# multishield.net
KiCad netlist of a schematic drawn in EAGLE
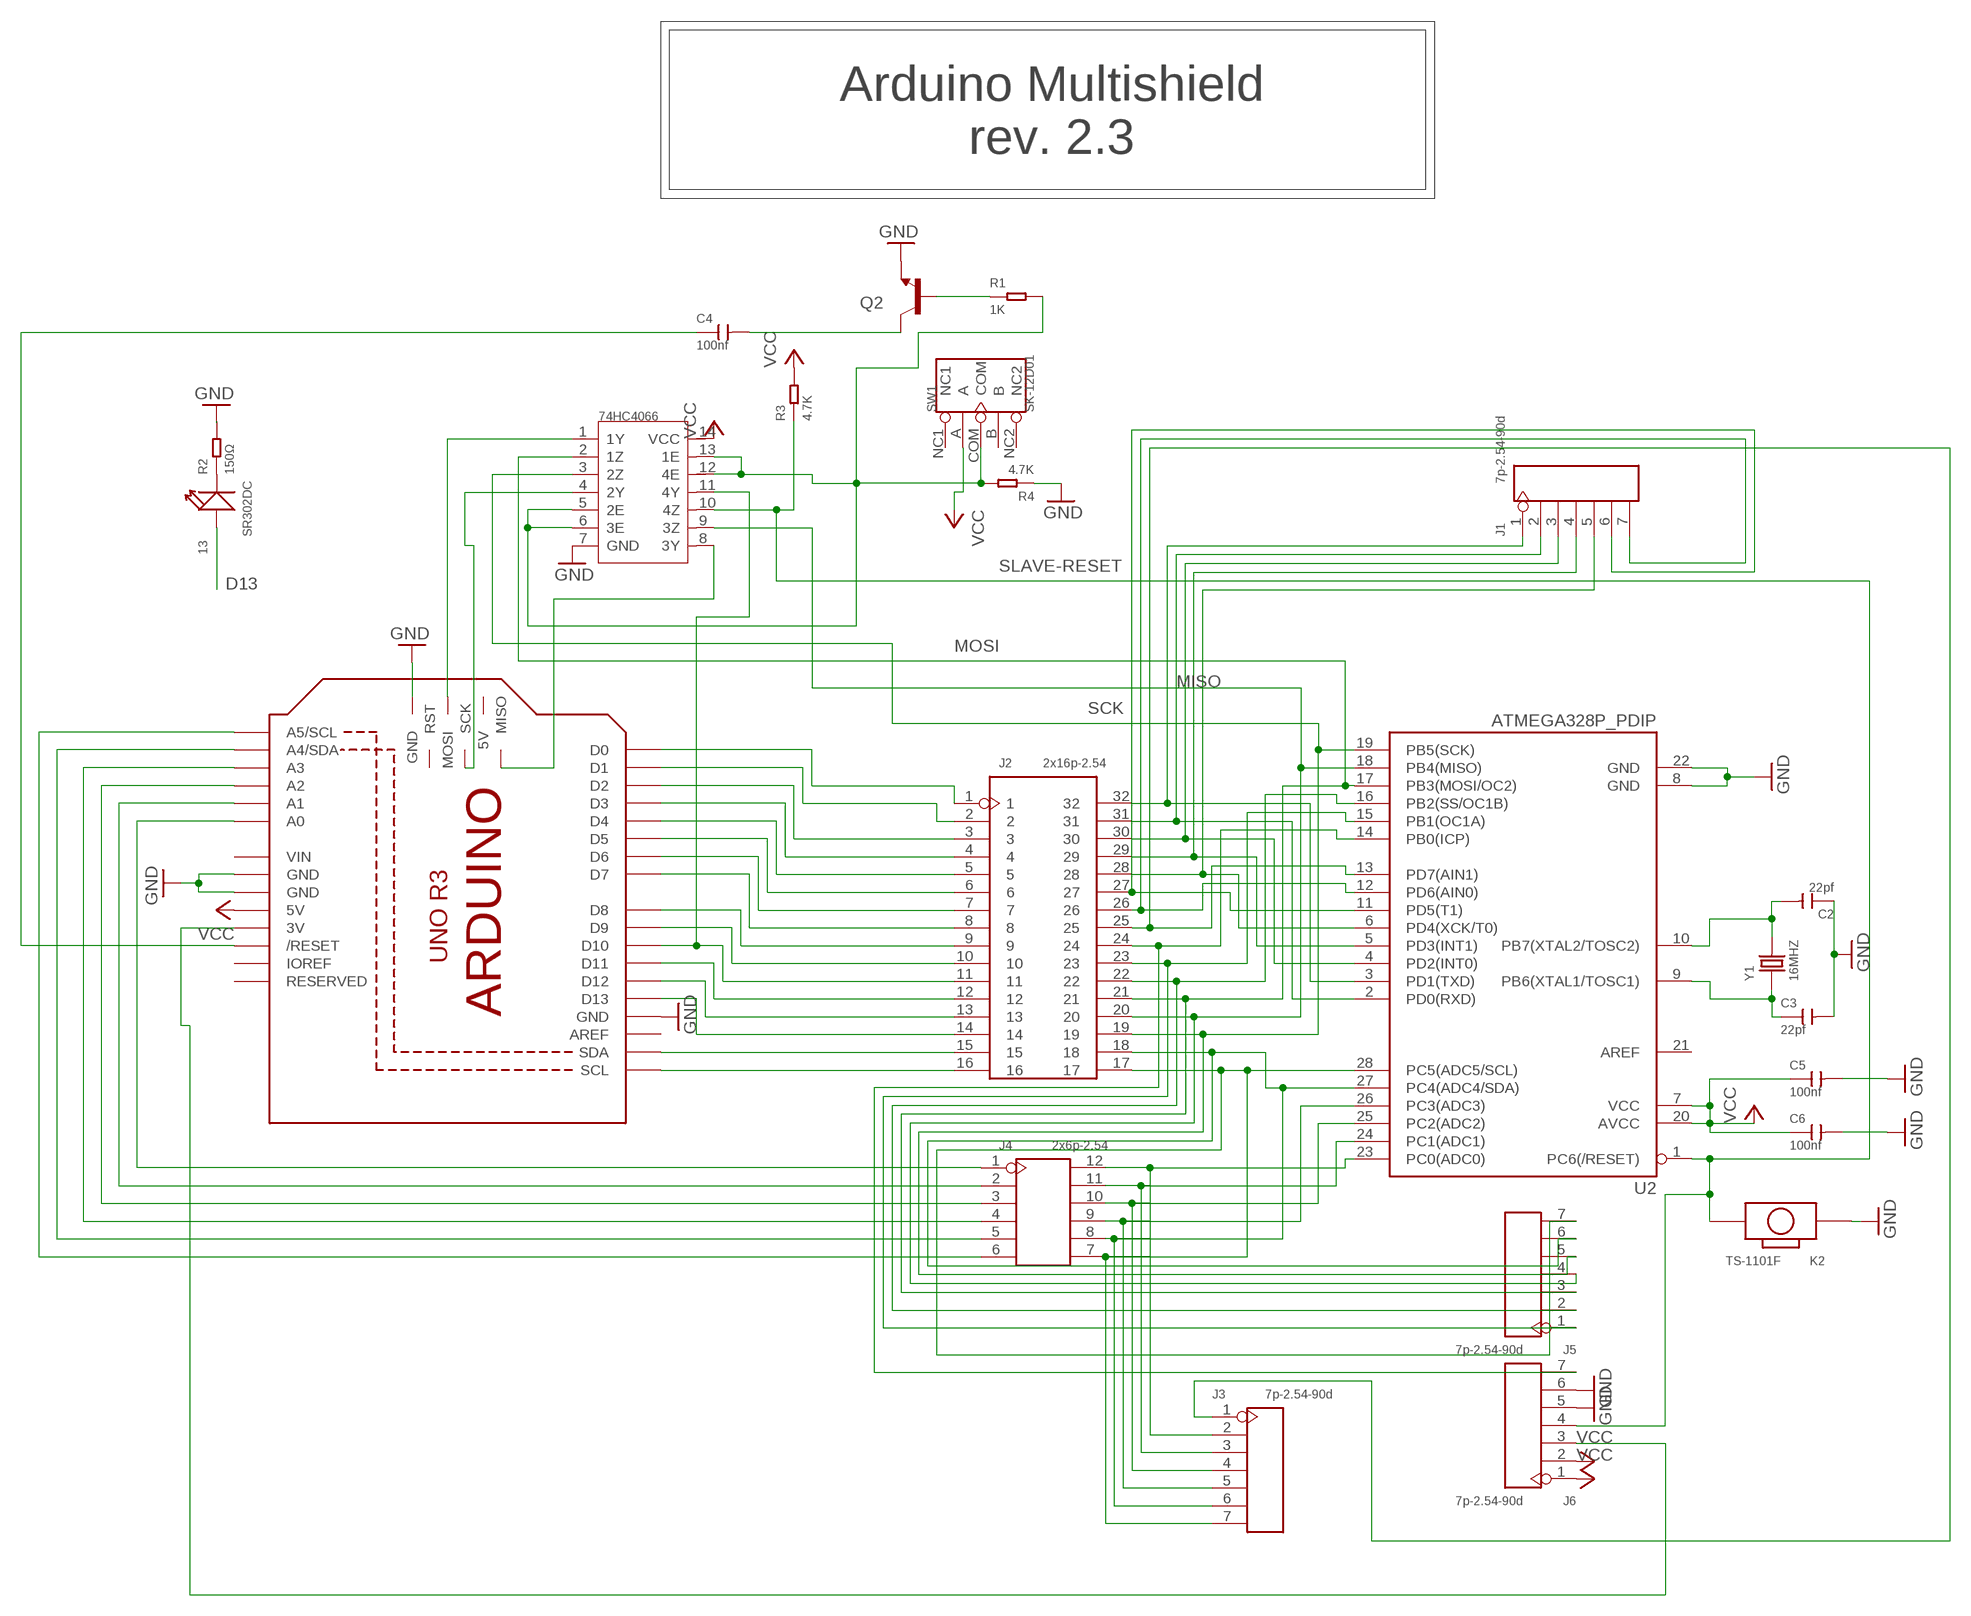
[diagram p0: schematic, sheet 1]

(export (version "E")
  (design (tool "Eeschema 10.0.6"))
  (components
    (comp (ref "13")
      (value "SR302DC")
      (footprint "eagle-import:LED2-2.54-D3.0MM")
      (libsource (lib "eagle-import") (part "DIP-LED-RED-RED(2P-D3MM)"))
    )
    (comp (ref "C2")
      (value "22pf")
      (footprint "eagle-import:CERAMIC-2.54")
      (fields (field (name "MPN") "CS1-D5Y5V2A104ZSP"))
      (libsource (lib "eagle-import") (part "DIP-CERAMIC-DISC-22PF-50V-10%-NPO(D4.0MM)"))
    )
    (comp (ref "C3")
      (value "22pf")
      (footprint "eagle-import:CERAMIC-2.54")
      (fields (field (name "MPN") "CS1-D5Y5V2A104ZSP"))
      (libsource (lib "eagle-import") (part "DIP-CERAMIC-DISC-22PF-50V-10%-NPO(D4.0MM)"))
    )
    (comp (ref "C4")
      (value "100nf")
      (footprint "eagle-import:CERAMIC-2.54")
      (fields (field (name "MPN") "CC1-F5SL2A101KSPW"))
      (libsource (lib "eagle-import") (part "DIP-CERAMIC-DISC-100NF-50V-Y5V(D5.0MM)"))
    )
    (comp (ref "C5")
      (value "100nf")
      (footprint "eagle-import:CERAMIC-2.54")
      (fields (field (name "MPN") "CC1-F5SL2A101KSPW"))
      (libsource (lib "eagle-import") (part "DIP-CERAMIC-DISC-100NF-50V-Y5V(D5.0MM)"))
    )
    (comp (ref "C6")
      (value "100nf")
      (footprint "eagle-import:CERAMIC-2.54")
      (fields (field (name "MPN") "CC1-F5SL2A101KSPW"))
      (libsource (lib "eagle-import") (part "DIP-CERAMIC-DISC-100NF-50V-Y5V(D5.0MM)"))
    )
    (comp (ref "J1")
      (value "7p-2.54-90d")
      (footprint "eagle-import:H7-2.54-90D-MALE")
      (fields (field (name "MPN") "P125-1107A0BR138A1"))
      (libsource (lib "eagle-import") (part "DIP-BLACK-MALE-HEADER(7P-2.54-90D)"))
    )
    (comp (ref "J2")
      (value "2x16p-2.54")
      (footprint "eagle-import:H2X16-2.54")
      (fields (field (name "MPN") "P125-1232A0AS116A1"))
      (libsource (lib "eagle-import") (part "DIP-BLACK-MALE-HEADER-VERT(2X16P-2.54)"))
    )
    (comp (ref "J3")
      (value "7p-2.54-90d")
      (footprint "eagle-import:H7-2.54-90D-MALE")
      (fields (field (name "MPN") "P125-1107A0BR138A1"))
      (libsource (lib "eagle-import") (part "DIP-BLACK-MALE-HEADER(7P-2.54-90D)"))
    )
    (comp (ref "J4")
      (value "2x6p-2.54")
      (footprint "eagle-import:H2X6-2.54")
      (fields (field (name "MPN") "P125-1212A0AS116A1"))
      (libsource (lib "eagle-import") (part "DIP-BLACK-MALE-HEADER(2X6P-2.54)"))
    )
    (comp (ref "J5")
      (value "7p-2.54-90d")
      (footprint "eagle-import:H7-2.54-90D-MALE")
      (fields (field (name "MPN") "P125-1107A0BR138A1"))
      (libsource (lib "eagle-import") (part "DIP-BLACK-MALE-HEADER(7P-2.54-90D)"))
    )
    (comp (ref "J6")
      (value "7p-2.54-90d")
      (footprint "eagle-import:H7-2.54-90D-MALE")
      (fields (field (name "MPN") "P125-1107A0BR138A1"))
      (libsource (lib "eagle-import") (part "DIP-BLACK-MALE-HEADER(7P-2.54-90D)"))
    )
    (comp (ref "K2")
      (value "TS-1101F")
      (footprint "eagle-import:SW2-3.4X6.0X3.55MM-90D")
      (libsource (lib "eagle-import") (part "DIP-BUTTON-FRONT-WHITE(2P-3.4X6MM)"))
    )
    (comp (ref "M1")
      (value "ARDUINO_R3_ICSP")
      (footprint "eagle-import:ARDUINOR3_ICSP")
      (libsource (lib "eagle-import") (part "ARDUINO_R3_ICSP"))
    )
    (comp (ref "Q2")
      (value "TRANSISTOR_NPNBC547")
      (footprint "eagle-import:TO-92-AMMO")
      (libsource (lib "eagle-import") (part "TRANSISTOR_NPNBC547"))
    )
    (comp (ref "R1")
      (value "1K")
      (footprint "eagle-import:PR-D2.3XL6.5MM")
      (fields (field (name "MPN") "FHCFR-1/4W-102J"))
      (libsource (lib "eagle-import") (part "DIP-RES-1K-5%-1/4W(PR-D2.3XL6.5MM)"))
    )
    (comp (ref "R2")
      (value "150Ω")
      (footprint "eagle-import:PR-D2.3XL6.5MM")
      (fields (field (name "MPN") "FHCFR-1/4W-102J"))
      (libsource (lib "eagle-import") (part "DIP-RES-1K-5%-1/4W(PR-D2.3XL6.5MM)"))
    )
    (comp (ref "R3")
      (value "4.7K")
      (footprint "eagle-import:PR-D2.3XL6.5MM")
      (fields (field (name "MPN") "FHCFR-1/4W-472J"))
      (libsource (lib "eagle-import") (part "DIP-RES-4.7K-5%-1/4W(PR-D2.3XL6.5MM)"))
    )
    (comp (ref "R4")
      (value "4.7K")
      (footprint "eagle-import:PR-D2.3XL6.5MM")
      (fields (field (name "MPN") "FHCFR-1/4W-472J"))
      (libsource (lib "eagle-import") (part "DIP-RES-4.7K-5%-1/4W(PR-D2.3XL6.5MM)"))
    )
    (comp (ref "SW1")
      (value "SK-12D01")
      (footprint "eagle-import:SW5-2.0-8.8X4.4X4.7MM-90D")
      (libsource (lib "eagle-import") (part "DIP-TOGGLE-SWITCH-ON-ON(3+2P-8.8X4.6MM)"))
    )
    (comp (ref "U1")
      (value "AD595AQ-DIP14")
      (footprint "eagle-import:DIP14-2.54-17.24X6.35MM")
      (fields (field (name "MPN") "AD595AQ"))
      (libsource (lib "eagle-import") (part "74HC4066(DIP14)"))
    )
    (comp (ref "U2")
      (value "ATMEGA328P_PDIP")
      (footprint "eagle-import:DIL28-3")
      (libsource (lib "eagle-import") (part "ATMEGA328P_PDIP"))
    )
    (comp (ref "Y1")
      (value "16MHZ")
      (footprint "eagle-import:HC49US")
      (fields (field (name "MPN") "49S/18PF"))
      (libsource (lib "eagle-import") (part "DIP-CRYSTAL-16MHZ-18PF-30PPM-50R(HC49US)"))
    )
  )
  (nets
    (net (code "1") (name "/MISO") (class "Default")
      (node (ref "J2") (pin "20") (pinfunction "20_20") (pintype "bidirectional"))
      (node (ref "J5") (pin "4") (pinfunction "4_4") (pintype "bidirectional"))
      (node (ref "U1") (pin "9") (pinfunction "3Z_9") (pintype "bidirectional"))
      (node (ref "U2") (pin "18") (pinfunction "PB4(MISO)_18") (pintype "bidirectional"))
    )
    (net (code "2") (name "/MOSI") (class "Default")
      (node (ref "J2") (pin "21") (pinfunction "21_21") (pintype "bidirectional"))
      (node (ref "J5") (pin "3") (pinfunction "3_3") (pintype "bidirectional"))
      (node (ref "U1") (pin "2") (pinfunction "1Z_2") (pintype "bidirectional"))
      (node (ref "U2") (pin "17") (pinfunction "PB3(MOSI/OC2)_17") (pintype "bidirectional"))
    )
    (net (code "3") (name "/SCK") (class "Default")
      (node (ref "13") (pin "A") (pinfunction "+_A") (pintype "passive"))
      (node (ref "J2") (pin "19") (pinfunction "19_19") (pintype "bidirectional"))
      (node (ref "J5") (pin "5") (pinfunction "5_5") (pintype "bidirectional"))
      (node (ref "U1") (pin "3") (pinfunction "2Z_3") (pintype "bidirectional"))
      (node (ref "U2") (pin "19") (pinfunction "PB5(SCK)_19") (pintype "bidirectional"))
    )
    (net (code "4") (name "/SLAVE-RESET") (class "Default")
      (node (ref "J6") (pin "4") (pinfunction "4_4") (pintype "bidirectional"))
      (node (ref "K2") (pin "P$2") (pinfunction "2_P$2") (pintype "bidirectional"))
      (node (ref "R3") (pin "1") (pinfunction "1_1") (pintype "passive"))
      (node (ref "U1") (pin "10") (pinfunction "4Z_10") (pintype "bidirectional"))
      (node (ref "U2") (pin "1") (pinfunction "PC6(/RESET)_1") (pintype "bidirectional"))
    )
    (net (code "5") (name "/VIN") (class "Default")
      (node (ref "M1") (pin "VIN") (pinfunction "VIN_VIN") (pintype "power_in"))
    )
    (net (code "6") (name "GND") (class "Default")
      (node (ref "C2") (pin "1") (pinfunction "1_1") (pintype "passive"))
      (node (ref "C3") (pin "2") (pinfunction "2_2") (pintype "passive"))
      (node (ref "C5") (pin "2") (pinfunction "2_2") (pintype "passive"))
      (node (ref "C6") (pin "2") (pinfunction "2_2") (pintype "passive"))
      (node (ref "J6") (pin "5") (pinfunction "5_5") (pintype "bidirectional"))
      (node (ref "J6") (pin "6") (pinfunction "6_6") (pintype "bidirectional"))
      (node (ref "K2") (pin "P$1") (pinfunction "1_P$1") (pintype "bidirectional"))
      (node (ref "M1") (pin "GND") (pinfunction "GND_GND") (pintype "power_in"))
      (node (ref "M1") (pin "GND@1") (pinfunction "GND_GND@1") (pintype "power_in"))
      (node (ref "M1") (pin "GND@2") (pinfunction "GND_GND@2") (pintype "passive"))
      (node (ref "M1") (pin "GND@3") (pinfunction "GND_GND@3") (pintype "power_in"))
      (node (ref "Q2") (pin "3") (pinfunction "E_3") (pintype "passive"))
      (node (ref "R2") (pin "2") (pinfunction "2_2") (pintype "passive"))
      (node (ref "R4") (pin "1") (pinfunction "1_1") (pintype "passive"))
      (node (ref "U1") (pin "7") (pinfunction "GND_7") (pintype "bidirectional"))
      (node (ref "U2") (pin "22") (pinfunction "GND_22") (pintype "bidirectional"))
      (node (ref "U2") (pin "8") (pinfunction "GND_8") (pintype "bidirectional"))
    )
    (net (code "7") (name "Net-(13--)") (class "Default")
      (node (ref "13") (pin "K") (pinfunction "-_K") (pintype "passive"))
      (node (ref "R2") (pin "1") (pinfunction "1_1") (pintype "passive"))
    )
    (net (code "8") (name "Net-(J2-Pad1)") (class "Default")
      (node (ref "J2") (pin "1") (pinfunction "1_1") (pintype "bidirectional"))
      (node (ref "M1") (pin "D0") (pinfunction "D0_D0") (pintype "bidirectional"))
    )
    (net (code "9") (name "Net-(J2-Pad2)") (class "Default")
      (node (ref "J2") (pin "2") (pinfunction "2_2") (pintype "bidirectional"))
      (node (ref "M1") (pin "D1") (pinfunction "D1_D1") (pintype "bidirectional"))
    )
    (net (code "10") (name "Net-(J2-Pad3)") (class "Default")
      (node (ref "J2") (pin "3") (pinfunction "3_3") (pintype "bidirectional"))
      (node (ref "M1") (pin "D2") (pinfunction "D2_D2") (pintype "bidirectional"))
    )
    (net (code "11") (name "Net-(J2-Pad4)") (class "Default")
      (node (ref "J2") (pin "4") (pinfunction "4_4") (pintype "bidirectional"))
      (node (ref "M1") (pin "D3") (pinfunction "D3_D3") (pintype "bidirectional"))
    )
    (net (code "12") (name "Net-(J2-Pad5)") (class "Default")
      (node (ref "J2") (pin "5") (pinfunction "5_5") (pintype "bidirectional"))
      (node (ref "M1") (pin "D4") (pinfunction "D4_D4") (pintype "bidirectional"))
    )
    (net (code "13") (name "Net-(J2-Pad6)") (class "Default")
      (node (ref "J2") (pin "6") (pinfunction "6_6") (pintype "bidirectional"))
      (node (ref "M1") (pin "D5") (pinfunction "D5_D5") (pintype "bidirectional"))
    )
    (net (code "14") (name "Net-(J2-Pad7)") (class "Default")
      (node (ref "J2") (pin "7") (pinfunction "7_7") (pintype "bidirectional"))
      (node (ref "M1") (pin "D6") (pinfunction "D6_D6") (pintype "bidirectional"))
    )
    (net (code "15") (name "Net-(J2-Pad8)") (class "Default")
      (node (ref "J2") (pin "8") (pinfunction "8_8") (pintype "bidirectional"))
      (node (ref "M1") (pin "D7") (pinfunction "D7_D7") (pintype "bidirectional"))
    )
    (net (code "16") (name "Net-(J2-Pad9)") (class "Default")
      (node (ref "J2") (pin "9") (pinfunction "9_9") (pintype "bidirectional"))
      (node (ref "M1") (pin "D8") (pinfunction "D8_D8") (pintype "bidirectional"))
    )
    (net (code "17") (name "Net-(J2-Pad10)") (class "Default")
      (node (ref "J2") (pin "10") (pinfunction "10_10") (pintype "bidirectional"))
      (node (ref "M1") (pin "D9") (pinfunction "D9_D9") (pintype "bidirectional"))
    )
    (net (code "18") (name "Net-(J2-Pad12)") (class "Default")
      (node (ref "J2") (pin "12") (pinfunction "12_12") (pintype "bidirectional"))
      (node (ref "M1") (pin "D11") (pinfunction "D11_D11") (pintype "bidirectional"))
    )
    (net (code "19") (name "Net-(J2-Pad13)") (class "Default")
      (node (ref "J2") (pin "13") (pinfunction "13_13") (pintype "bidirectional"))
      (node (ref "M1") (pin "D12") (pinfunction "D12_D12") (pintype "bidirectional"))
    )
    (net (code "20") (name "Net-(J2-Pad14)") (class "Default")
      (node (ref "J2") (pin "14") (pinfunction "14_14") (pintype "bidirectional"))
      (node (ref "M1") (pin "D13") (pinfunction "D13_D13") (pintype "bidirectional"))
    )
    (net (code "21") (name "Net-(J2-Pad15)") (class "Default")
      (node (ref "J2") (pin "15") (pinfunction "15_15") (pintype "bidirectional"))
      (node (ref "M1") (pin "SDA") (pinfunction "SDA_SDA") (pintype "bidirectional"))
    )
    (net (code "22") (name "Net-(J2-Pad16)") (class "Default")
      (node (ref "J2") (pin "16") (pinfunction "16_16") (pintype "bidirectional"))
      (node (ref "M1") (pin "SCL") (pinfunction "SCL_SCL") (pintype "bidirectional"))
    )
    (net (code "23") (name "Net-(J4-Pad1)") (class "Default")
      (node (ref "J4") (pin "1") (pinfunction "1_1") (pintype "bidirectional"))
      (node (ref "M1") (pin "A0") (pinfunction "A0_A0") (pintype "bidirectional"))
    )
    (net (code "24") (name "Net-(J4-Pad2)") (class "Default")
      (node (ref "J4") (pin "2") (pinfunction "2_2") (pintype "bidirectional"))
      (node (ref "M1") (pin "A1") (pinfunction "A1_A1") (pintype "bidirectional"))
    )
    (net (code "25") (name "Net-(J4-Pad3)") (class "Default")
      (node (ref "J4") (pin "3") (pinfunction "3_3") (pintype "bidirectional"))
      (node (ref "M1") (pin "A2") (pinfunction "A2_A2") (pintype "bidirectional"))
    )
    (net (code "26") (name "Net-(J4-Pad4)") (class "Default")
      (node (ref "J4") (pin "4") (pinfunction "4_4") (pintype "bidirectional"))
      (node (ref "M1") (pin "A3") (pinfunction "A3_A3") (pintype "bidirectional"))
    )
    (net (code "27") (name "Net-(J6-Pad3)") (class "Default")
      (node (ref "J6") (pin "3") (pinfunction "3_3") (pintype "bidirectional"))
      (node (ref "M1") (pin "3V") (pinfunction "3V_3V") (pintype "power_in"))
    )
    (net (code "28") (name "Net-(M1-A4{slash}SDA)") (class "Default")
      (node (ref "J4") (pin "5") (pinfunction "5_5") (pintype "bidirectional"))
      (node (ref "M1") (pin "A4") (pinfunction "A4/SDA_A4") (pintype "bidirectional"))
    )
    (net (code "29") (name "Net-(M1-A5{slash}SCL)") (class "Default")
      (node (ref "J4") (pin "6") (pinfunction "6_6") (pintype "bidirectional"))
      (node (ref "M1") (pin "A5") (pinfunction "A5/SCL_A5") (pintype "bidirectional"))
    )
    (net (code "30") (name "Net-(M1-{slash}RESET)") (class "Default")
      (node (ref "C4") (pin "1") (pinfunction "1_1") (pintype "passive"))
      (node (ref "M1") (pin "RESET") (pinfunction "/RESET_RESET") (pintype "bidirectional"))
    )
    (net (code "31") (name "Net-(Q2-B)") (class "Default")
      (node (ref "Q2") (pin "2") (pinfunction "B_2") (pintype "passive"))
      (node (ref "R1") (pin "1") (pinfunction "1_1") (pintype "passive"))
    )
    (net (code "32") (name "Net-(Q2-C)") (class "Default")
      (node (ref "C4") (pin "2") (pinfunction "2_2") (pintype "passive"))
      (node (ref "Q2") (pin "1") (pinfunction "C_1") (pintype "passive"))
    )
    (net (code "33") (name "Net-(U1-1E)") (class "Default")
      (node (ref "R1") (pin "2") (pinfunction "2_2") (pintype "passive"))
      (node (ref "R4") (pin "2") (pinfunction "2_2") (pintype "passive"))
      (node (ref "SW1") (pin "COM") (pinfunction "COM_COM") (pintype "bidirectional"))
      (node (ref "U1") (pin "12") (pinfunction "4E_12") (pintype "bidirectional"))
      (node (ref "U1") (pin "13") (pinfunction "1E_13") (pintype "bidirectional"))
      (node (ref "U1") (pin "5") (pinfunction "2E_5") (pintype "bidirectional"))
      (node (ref "U1") (pin "6") (pinfunction "3E_6") (pintype "bidirectional"))
    )
    (net (code "34") (name "Net-(U1-1Y)") (class "Default")
      (node (ref "M1") (pin "MOSI") (pinfunction "MOSI_MOSI") (pintype "passive"))
      (node (ref "U1") (pin "1") (pinfunction "1Y_1") (pintype "bidirectional"))
    )
    (net (code "35") (name "Net-(U1-2Y)") (class "Default")
      (node (ref "M1") (pin "SCK") (pinfunction "SCK_SCK") (pintype "passive"))
      (node (ref "U1") (pin "4") (pinfunction "2Y_4") (pintype "bidirectional"))
    )
    (net (code "36") (name "Net-(U1-3Y)") (class "Default")
      (node (ref "M1") (pin "MISO") (pinfunction "MISO_MISO") (pintype "passive"))
      (node (ref "U1") (pin "8") (pinfunction "3Y_8") (pintype "bidirectional"))
    )
    (net (code "37") (name "Net-(U1-4Y)") (class "Default")
      (node (ref "J2") (pin "11") (pinfunction "11_11") (pintype "bidirectional"))
      (node (ref "M1") (pin "D10") (pinfunction "D10_D10") (pintype "bidirectional"))
      (node (ref "U1") (pin "11") (pinfunction "4Y_11") (pintype "bidirectional"))
    )
    (net (code "38") (name "Net-(U2-PB0(ICP))") (class "Default")
      (node (ref "J2") (pin "24") (pinfunction "24_24") (pintype "bidirectional"))
      (node (ref "J6") (pin "7") (pinfunction "7_7") (pintype "bidirectional"))
      (node (ref "U2") (pin "14") (pinfunction "PB0(ICP)_14") (pintype "bidirectional"))
    )
    (net (code "39") (name "Net-(U2-PB1(OC1A))") (class "Default")
      (node (ref "J2") (pin "23") (pinfunction "23_23") (pintype "bidirectional"))
      (node (ref "J5") (pin "1") (pinfunction "1_1") (pintype "bidirectional"))
      (node (ref "U2") (pin "15") (pinfunction "PB1(OC1A)_15") (pintype "bidirectional"))
    )
    (net (code "40") (name "Net-(U2-PB2(SS{slash}OC1B))") (class "Default")
      (node (ref "J2") (pin "22") (pinfunction "22_22") (pintype "bidirectional"))
      (node (ref "J5") (pin "2") (pinfunction "2_2") (pintype "bidirectional"))
      (node (ref "U2") (pin "16") (pinfunction "PB2(SS/OC1B)_16") (pintype "bidirectional"))
    )
    (net (code "41") (name "Net-(U2-PB6(XTAL1{slash}TOSC1))") (class "Default")
      (node (ref "C3") (pin "1") (pinfunction "1_1") (pintype "passive"))
      (node (ref "U2") (pin "9") (pinfunction "PB6(XTAL1/TOSC1)_9") (pintype "bidirectional"))
      (node (ref "Y1") (pin "1") (pinfunction "1_1") (pintype "passive"))
    )
    (net (code "42") (name "Net-(U2-PB7(XTAL2{slash}TOSC2))") (class "Default")
      (node (ref "C2") (pin "2") (pinfunction "2_2") (pintype "passive"))
      (node (ref "U2") (pin "10") (pinfunction "PB7(XTAL2/TOSC2)_10") (pintype "bidirectional"))
      (node (ref "Y1") (pin "2") (pinfunction "2_2") (pintype "passive"))
    )
    (net (code "43") (name "Net-(U2-PC0(ADC0))") (class "Default")
      (node (ref "J3") (pin "2") (pinfunction "2_2") (pintype "bidirectional"))
      (node (ref "J4") (pin "12") (pinfunction "12_12") (pintype "bidirectional"))
      (node (ref "U2") (pin "23") (pinfunction "PC0(ADC0)_23") (pintype "bidirectional"))
    )
    (net (code "44") (name "Net-(U2-PC1(ADC1))") (class "Default")
      (node (ref "J3") (pin "3") (pinfunction "3_3") (pintype "bidirectional"))
      (node (ref "J4") (pin "11") (pinfunction "11_11") (pintype "bidirectional"))
      (node (ref "U2") (pin "24") (pinfunction "PC1(ADC1)_24") (pintype "bidirectional"))
    )
    (net (code "45") (name "Net-(U2-PC2(ADC2))") (class "Default")
      (node (ref "J3") (pin "4") (pinfunction "4_4") (pintype "bidirectional"))
      (node (ref "J4") (pin "10") (pinfunction "10_10") (pintype "bidirectional"))
      (node (ref "U2") (pin "25") (pinfunction "PC2(ADC2)_25") (pintype "bidirectional"))
    )
    (net (code "46") (name "Net-(U2-PC3(ADC3))") (class "Default")
      (node (ref "J3") (pin "5") (pinfunction "5_5") (pintype "bidirectional"))
      (node (ref "J4") (pin "9") (pinfunction "9_9") (pintype "bidirectional"))
      (node (ref "U2") (pin "26") (pinfunction "PC3(ADC3)_26") (pintype "bidirectional"))
    )
    (net (code "47") (name "Net-(U2-PC4(ADC4{slash}SDA))") (class "Default")
      (node (ref "J2") (pin "18") (pinfunction "18_18") (pintype "bidirectional"))
      (node (ref "J3") (pin "6") (pinfunction "6_6") (pintype "bidirectional"))
      (node (ref "J4") (pin "8") (pinfunction "8_8") (pintype "bidirectional"))
      (node (ref "J5") (pin "6") (pinfunction "6_6") (pintype "bidirectional"))
      (node (ref "U2") (pin "27") (pinfunction "PC4(ADC4/SDA)_27") (pintype "bidirectional"))
    )
    (net (code "48") (name "Net-(U2-PC5(ADC5{slash}SCL))") (class "Default")
      (node (ref "J2") (pin "17") (pinfunction "17_17") (pintype "bidirectional"))
      (node (ref "J3") (pin "7") (pinfunction "7_7") (pintype "bidirectional"))
      (node (ref "J4") (pin "7") (pinfunction "7_7") (pintype "bidirectional"))
      (node (ref "J5") (pin "7") (pinfunction "7_7") (pintype "bidirectional"))
      (node (ref "U2") (pin "28") (pinfunction "PC5(ADC5/SCL)_28") (pintype "bidirectional"))
    )
    (net (code "49") (name "Net-(U2-PD0(RXD))") (class "Default")
      (node (ref "J1") (pin "2") (pinfunction "2_2") (pintype "bidirectional"))
      (node (ref "J2") (pin "31") (pinfunction "31_31") (pintype "bidirectional"))
      (node (ref "U2") (pin "2") (pinfunction "PD0(RXD)_2") (pintype "bidirectional"))
    )
    (net (code "50") (name "Net-(U2-PD1(TXD))") (class "Default")
      (node (ref "J1") (pin "1") (pinfunction "1_1") (pintype "bidirectional"))
      (node (ref "J2") (pin "32") (pinfunction "32_32") (pintype "bidirectional"))
      (node (ref "U2") (pin "3") (pinfunction "PD1(TXD)_3") (pintype "bidirectional"))
    )
    (net (code "51") (name "Net-(U2-PD2(INT0))") (class "Default")
      (node (ref "J1") (pin "3") (pinfunction "3_3") (pintype "bidirectional"))
      (node (ref "J2") (pin "30") (pinfunction "30_30") (pintype "bidirectional"))
      (node (ref "U2") (pin "4") (pinfunction "PD2(INT0)_4") (pintype "bidirectional"))
    )
    (net (code "52") (name "Net-(U2-PD3(INT1))") (class "Default")
      (node (ref "J1") (pin "4") (pinfunction "4_4") (pintype "bidirectional"))
      (node (ref "J2") (pin "29") (pinfunction "29_29") (pintype "bidirectional"))
      (node (ref "U2") (pin "5") (pinfunction "PD3(INT1)_5") (pintype "bidirectional"))
    )
    (net (code "53") (name "Net-(U2-PD4(XCK{slash}T0))") (class "Default")
      (node (ref "J1") (pin "5") (pinfunction "5_5") (pintype "bidirectional"))
      (node (ref "J2") (pin "28") (pinfunction "28_28") (pintype "bidirectional"))
      (node (ref "U2") (pin "6") (pinfunction "PD4(XCK/T0)_6") (pintype "bidirectional"))
    )
    (net (code "54") (name "Net-(U2-PD5(T1))") (class "Default")
      (node (ref "J1") (pin "6") (pinfunction "6_6") (pintype "bidirectional"))
      (node (ref "J2") (pin "27") (pinfunction "27_27") (pintype "bidirectional"))
      (node (ref "U2") (pin "11") (pinfunction "PD5(T1)_11") (pintype "bidirectional"))
    )
    (net (code "55") (name "Net-(U2-PD6(AIN0))") (class "Default")
      (node (ref "J1") (pin "7") (pinfunction "7_7") (pintype "bidirectional"))
      (node (ref "J2") (pin "26") (pinfunction "26_26") (pintype "bidirectional"))
      (node (ref "U2") (pin "12") (pinfunction "PD6(AIN0)_12") (pintype "bidirectional"))
    )
    (net (code "56") (name "Net-(U2-PD7(AIN1))") (class "Default")
      (node (ref "J2") (pin "25") (pinfunction "25_25") (pintype "bidirectional"))
      (node (ref "J3") (pin "1") (pinfunction "1_1") (pintype "bidirectional"))
      (node (ref "U2") (pin "13") (pinfunction "PD7(AIN1)_13") (pintype "bidirectional"))
    )
    (net (code "57") (name "VCC") (class "Default")
      (node (ref "C5") (pin "1") (pinfunction "1_1") (pintype "passive"))
      (node (ref "C6") (pin "1") (pinfunction "1_1") (pintype "passive"))
      (node (ref "J6") (pin "1") (pinfunction "1_1") (pintype "bidirectional"))
      (node (ref "J6") (pin "2") (pinfunction "2_2") (pintype "bidirectional"))
      (node (ref "M1") (pin "5V") (pinfunction "5V_5V") (pintype "power_in"))
      (node (ref "R3") (pin "2") (pinfunction "2_2") (pintype "passive"))
      (node (ref "SW1") (pin "A") (pinfunction "A_A") (pintype "bidirectional"))
      (node (ref "U1") (pin "14") (pinfunction "VCC_14") (pintype "bidirectional"))
      (node (ref "U2") (pin "20") (pinfunction "AVCC_20") (pintype "bidirectional"))
      (node (ref "U2") (pin "7") (pinfunction "VCC_7") (pintype "bidirectional"))
    )
    (net (code "58") (name "unconnected-(M1-5V-Pad5V_ICSP)") (class "Default")
      (node (ref "M1") (pin "5V_ICSP") (pinfunction "5V_5V_ICSP") (pintype "passive"))
    )
    (net (code "59") (name "unconnected-(M1-PadAREF)") (class "Default")
      (node (ref "M1") (pin "AREF") (pinfunction "AREF_AREF") (pintype "bidirectional"))
    )
    (net (code "60") (name "unconnected-(M1-PadIOREF)") (class "Default")
      (node (ref "M1") (pin "IOREF") (pinfunction "IOREF_IOREF") (pintype "output"))
    )
    (net (code "61") (name "unconnected-(M1-PadRESERVED)") (class "Default")
      (node (ref "M1") (pin "RESERVED") (pinfunction "RESERVED_RESERVED") (pintype "no_connect"))
    )
    (net (code "62") (name "unconnected-(M1-RST-PadRESET_ICSP)") (class "Default")
      (node (ref "M1") (pin "RESET_ICSP") (pinfunction "RST_RESET_ICSP") (pintype "passive"))
    )
    (net (code "63") (name "unconnected-(SW1-PadB)") (class "Default")
      (node (ref "SW1") (pin "B") (pinfunction "B_B") (pintype "bidirectional"))
    )
    (net (code "64") (name "unconnected-(SW1-PadNC1)") (class "Default")
      (node (ref "SW1") (pin "NC1") (pinfunction "NC1_NC1") (pintype "bidirectional"))
    )
    (net (code "65") (name "unconnected-(SW1-PadNC2)") (class "Default")
      (node (ref "SW1") (pin "NC2") (pinfunction "NC2_NC2") (pintype "bidirectional"))
    )
    (net (code "66") (name "unconnected-(U2-AREF-Pad21)") (class "Default")
      (node (ref "U2") (pin "21") (pinfunction "AREF_21") (pintype "bidirectional"))
    )
  )
)
